# V2_2.net
KiCad netlist of a schematic drawn in EAGLE
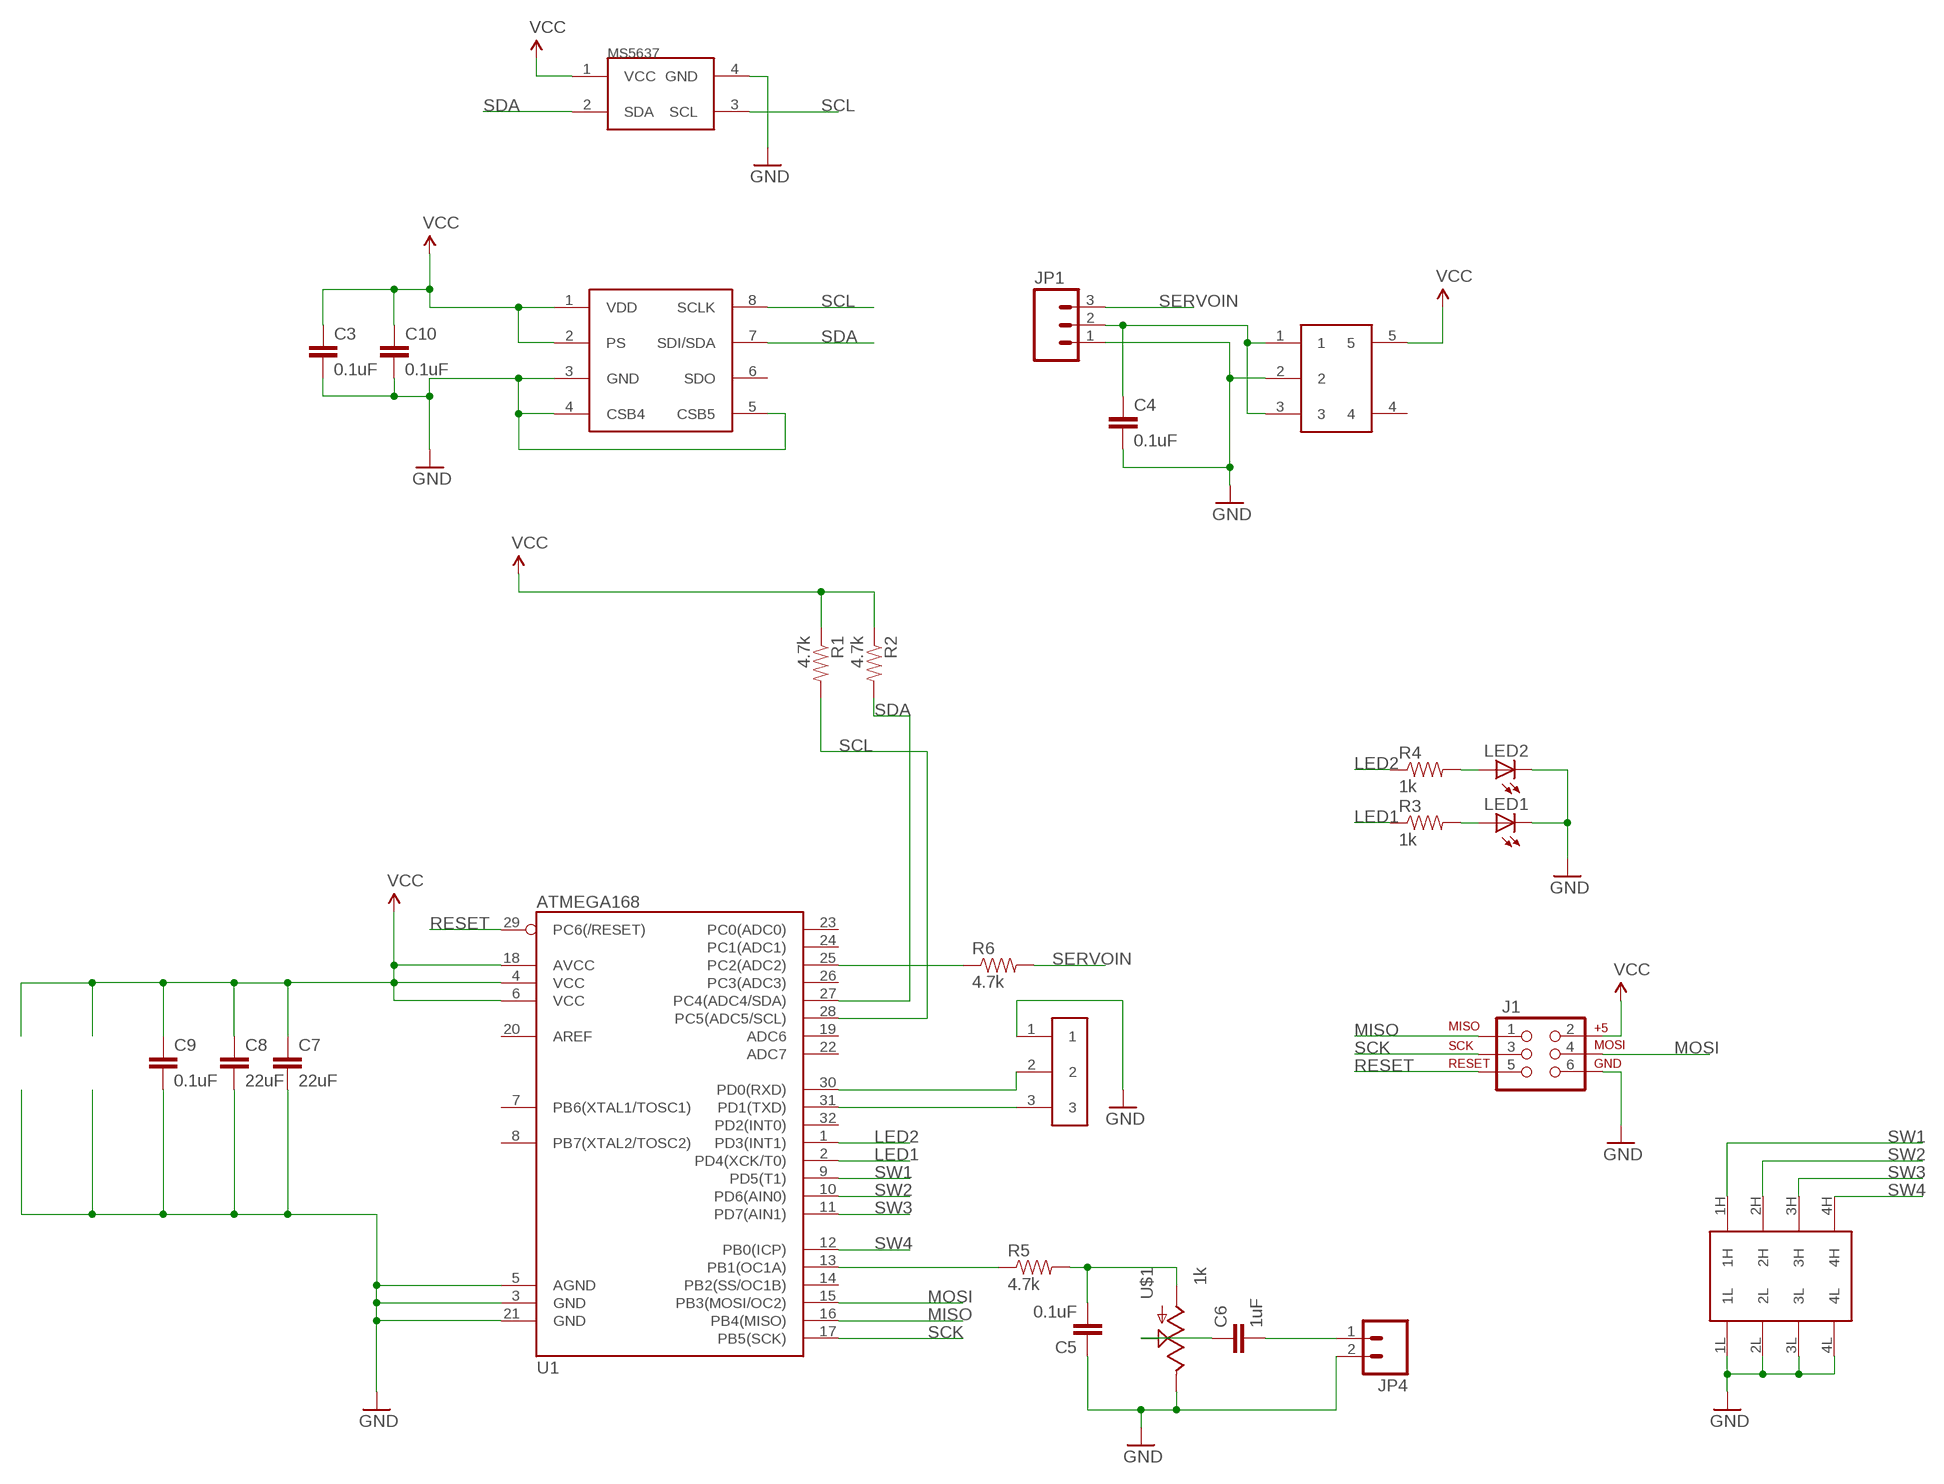
[diagram p0: schematic, sheet 1]

(export (version "E")
  (design (tool "Eeschema 10.0.6"))
  (components
    (comp (ref "C3")
      (value "0.1uF")
      (footprint "eagle-import:0603-CAP")
      (libsource (lib "eagle-import") (part "CAP0603-CAP"))
    )
    (comp (ref "C4")
      (value "0.1uF")
      (footprint "eagle-import:0603-CAP")
      (libsource (lib "eagle-import") (part "CAP0603-CAP"))
    )
    (comp (ref "C5")
      (value "0.1uF")
      (footprint "eagle-import:0603-CAP")
      (libsource (lib "eagle-import") (part "CAP0603-CAP"))
    )
    (comp (ref "C6")
      (value "1uF")
      (footprint "eagle-import:0603-CAP")
      (libsource (lib "eagle-import") (part "CAP0603-CAP"))
    )
    (comp (ref "C7")
      (value "22uF")
      (footprint "eagle-import:0805")
      (libsource (lib "eagle-import") (part "CAP0805"))
    )
    (comp (ref "C8")
      (value "22uF")
      (footprint "eagle-import:0805")
      (libsource (lib "eagle-import") (part "CAP0805"))
    )
    (comp (ref "C9")
      (value "0.1uF")
      (footprint "eagle-import:0603-CAP")
      (libsource (lib "eagle-import") (part "CAP0603-CAP"))
    )
    (comp (ref "C10")
      (value "0.1uF")
      (footprint "eagle-import:0603-CAP")
      (libsource (lib "eagle-import") (part "CAP0603-CAP"))
    )
    (comp (ref "J1")
      (value "AVR_SPI_PRG_6NS")
      (footprint "eagle-import:2X3-NS")
      (libsource (lib "eagle-import") (part "AVR_SPI_PRG_6NS"))
    )
    (comp (ref "JP1")
      (value "M03PTH")
      (footprint "eagle-import:1X03")
      (libsource (lib "eagle-import") (part "M03PTH"))
    )
    (comp (ref "JP4")
      (value "M02PTH")
      (footprint "eagle-import:1X02")
      (libsource (lib "eagle-import") (part "M02PTH"))
    )
    (comp (ref "LED1")
      (value "LED0603")
      (footprint "eagle-import:LED-0603")
      (libsource (lib "eagle-import") (part "LED0603"))
    )
    (comp (ref "LED2")
      (value "LED0603")
      (footprint "eagle-import:LED-0603")
      (libsource (lib "eagle-import") (part "LED0603"))
    )
    (comp (ref "R1")
      (value "4.7k")
      (footprint "eagle-import:0603-RES")
      (libsource (lib "eagle-import") (part "RESISTOR0603-RES"))
    )
    (comp (ref "R2")
      (value "4.7k")
      (footprint "eagle-import:0603-RES")
      (libsource (lib "eagle-import") (part "RESISTOR0603-RES"))
    )
    (comp (ref "R3")
      (value "1k")
      (footprint "eagle-import:0603-RES")
      (libsource (lib "eagle-import") (part "RESISTOR0603-RES"))
    )
    (comp (ref "R4")
      (value "1k")
      (footprint "eagle-import:0603-RES")
      (libsource (lib "eagle-import") (part "RESISTOR0603-RES"))
    )
    (comp (ref "R5")
      (value "4.7k")
      (footprint "eagle-import:0603-RES")
      (libsource (lib "eagle-import") (part "RESISTOR0603-RES"))
    )
    (comp (ref "R6")
      (value "4.7k")
      (footprint "eagle-import:0603-RES")
      (libsource (lib "eagle-import") (part "RESISTOR0603-RES"))
    )
    (comp (ref "U$1")
      (value "1k")
      (footprint "eagle-import:BOURNS_3306KPW")
      (libsource (lib "eagle-import") (part "POTBOURNS_3306KPW"))
    )
    (comp (ref "U$2")
      (value "MS5611")
      (footprint "eagle-import:MS5611")
      (libsource (lib "eagle-import") (part "MS5611"))
    )
    (comp (ref "U$4")
      (value "MS5637")
      (footprint "eagle-import:MS5637")
      (libsource (lib "eagle-import") (part "MS5637"))
    )
    (comp (ref "U$5")
      (value "DIP_SWITCH")
      (footprint "eagle-import:DIPSWITCH4")
      (libsource (lib "eagle-import") (part "DIP_SWITCH"))
    )
    (comp (ref "U$6")
      (value "HEADER3")
      (footprint "eagle-import:PAD3_1X1")
      (libsource (lib "eagle-import") (part "HEADER3"))
    )
    (comp (ref "U$7")
      (value "SOT23-5")
      (footprint "eagle-import:SOT23-5")
      (libsource (lib "eagle-import") (part "SOT23-5"))
    )
    (comp (ref "U1")
      (value "ATMEGA168")
      (footprint "eagle-import:TQFP32-08")
      (libsource (lib "eagle-import") (part "ATMEGA168"))
    )
  )
  (nets
    (net (code "1") (name "/LED1") (class "Default")
      (node (ref "R3") (pin "1") (pinfunction "1_1") (pintype "passive"))
      (node (ref "U1") (pin "2") (pinfunction "PD4(XCK/T0)_2") (pintype "bidirectional"))
    )
    (net (code "2") (name "/LED2") (class "Default")
      (node (ref "R4") (pin "1") (pinfunction "1_1") (pintype "passive"))
      (node (ref "U1") (pin "1") (pinfunction "PD3(INT1)_1") (pintype "bidirectional"))
    )
    (net (code "3") (name "/MISO") (class "Default")
      (node (ref "J1") (pin "1") (pinfunction "1_1") (pintype "passive"))
      (node (ref "U1") (pin "16") (pinfunction "PB4(MISO)_16") (pintype "bidirectional"))
    )
    (net (code "4") (name "/MOSI") (class "Default")
      (node (ref "J1") (pin "4") (pinfunction "4_4") (pintype "passive"))
      (node (ref "U1") (pin "15") (pinfunction "PB3(MOSI/OC2)_15") (pintype "bidirectional"))
    )
    (net (code "5") (name "/RESET") (class "Default")
      (node (ref "J1") (pin "5") (pinfunction "5_5") (pintype "passive"))
      (node (ref "U1") (pin "29") (pinfunction "PC6(/RESET)_29") (pintype "bidirectional"))
    )
    (net (code "6") (name "/SCK") (class "Default")
      (node (ref "J1") (pin "3") (pinfunction "3_3") (pintype "passive"))
      (node (ref "U1") (pin "17") (pinfunction "PB5(SCK)_17") (pintype "bidirectional"))
    )
    (net (code "7") (name "/SCL") (class "Default")
      (node (ref "R1") (pin "2") (pinfunction "2_2") (pintype "passive"))
      (node (ref "U$2") (pin "8") (pinfunction "SCLK_8") (pintype "bidirectional"))
      (node (ref "U$4") (pin "3") (pinfunction "SCL_3") (pintype "bidirectional"))
      (node (ref "U1") (pin "28") (pinfunction "PC5(ADC5/SCL)_28") (pintype "bidirectional"))
    )
    (net (code "8") (name "/SDA") (class "Default")
      (node (ref "R2") (pin "2") (pinfunction "2_2") (pintype "passive"))
      (node (ref "U$2") (pin "7") (pinfunction "SDI/SDA_7") (pintype "bidirectional"))
      (node (ref "U$4") (pin "2") (pinfunction "SDA_2") (pintype "bidirectional"))
      (node (ref "U1") (pin "27") (pinfunction "PC4(ADC4/SDA)_27") (pintype "bidirectional"))
    )
    (net (code "9") (name "/SERVOIN") (class "Default")
      (node (ref "JP1") (pin "3") (pinfunction "3_3") (pintype "passive"))
      (node (ref "R6") (pin "2") (pinfunction "2_2") (pintype "passive"))
    )
    (net (code "10") (name "/SW1") (class "Default")
      (node (ref "U$5") (pin "1H") (pinfunction "1H_1H") (pintype "bidirectional"))
      (node (ref "U1") (pin "9") (pinfunction "PD5(T1)_9") (pintype "bidirectional"))
    )
    (net (code "11") (name "/SW2") (class "Default")
      (node (ref "U$5") (pin "2H") (pinfunction "2H_2H") (pintype "bidirectional"))
      (node (ref "U1") (pin "10") (pinfunction "PD6(AIN0)_10") (pintype "bidirectional"))
    )
    (net (code "12") (name "/SW3") (class "Default")
      (node (ref "U$5") (pin "3H") (pinfunction "3H_3H") (pintype "bidirectional"))
      (node (ref "U1") (pin "11") (pinfunction "PD7(AIN1)_11") (pintype "bidirectional"))
    )
    (net (code "13") (name "/SW4") (class "Default")
      (node (ref "U$5") (pin "4H") (pinfunction "4H_4H") (pintype "bidirectional"))
      (node (ref "U1") (pin "12") (pinfunction "PB0(ICP)_12") (pintype "bidirectional"))
    )
    (net (code "14") (name "GND") (class "Default")
      (node (ref "C10") (pin "2") (pinfunction "2_2") (pintype "passive"))
      (node (ref "C3") (pin "2") (pinfunction "2_2") (pintype "passive"))
      (node (ref "C4") (pin "2") (pinfunction "2_2") (pintype "passive"))
      (node (ref "C5") (pin "1") (pinfunction "1_1") (pintype "passive"))
      (node (ref "C7") (pin "2") (pinfunction "2_2") (pintype "passive"))
      (node (ref "C8") (pin "2") (pinfunction "2_2") (pintype "passive"))
      (node (ref "C9") (pin "2") (pinfunction "2_2") (pintype "passive"))
      (node (ref "J1") (pin "6") (pinfunction "6_6") (pintype "passive"))
      (node (ref "JP1") (pin "1") (pinfunction "1_1") (pintype "passive"))
      (node (ref "JP4") (pin "2") (pinfunction "2_2") (pintype "passive"))
      (node (ref "LED1") (pin "C") (pinfunction "C_C") (pintype "passive"))
      (node (ref "LED2") (pin "C") (pinfunction "C_C") (pintype "passive"))
      (node (ref "U$1") (pin "1") (pinfunction "E_1") (pintype "passive"))
      (node (ref "U$2") (pin "3") (pinfunction "GND_3") (pintype "bidirectional"))
      (node (ref "U$2") (pin "4") (pinfunction "CSB4_4") (pintype "bidirectional"))
      (node (ref "U$2") (pin "5") (pinfunction "CSB5_5") (pintype "bidirectional"))
      (node (ref "U$4") (pin "4") (pinfunction "GND_4") (pintype "bidirectional"))
      (node (ref "U$5") (pin "1L") (pinfunction "1L_1L") (pintype "bidirectional"))
      (node (ref "U$5") (pin "2L") (pinfunction "2L_2L") (pintype "bidirectional"))
      (node (ref "U$5") (pin "3L") (pinfunction "3L_3L") (pintype "bidirectional"))
      (node (ref "U$5") (pin "4L") (pinfunction "4L_4L") (pintype "bidirectional"))
      (node (ref "U$6") (pin "1") (pinfunction "1_1") (pintype "bidirectional"))
      (node (ref "U$7") (pin "2") (pinfunction "2_2") (pintype "bidirectional"))
      (node (ref "U1") (pin "21") (pinfunction "GND_21") (pintype "bidirectional"))
      (node (ref "U1") (pin "3") (pinfunction "GND_3") (pintype "bidirectional"))
      (node (ref "U1") (pin "5") (pinfunction "AGND_5") (pintype "bidirectional"))
    )
    (net (code "15") (name "Net-(C4-Pad1)") (class "Default")
      (node (ref "C4") (pin "1") (pinfunction "1_1") (pintype "passive"))
      (node (ref "JP1") (pin "2") (pinfunction "2_2") (pintype "passive"))
      (node (ref "U$7") (pin "1") (pinfunction "1_1") (pintype "bidirectional"))
      (node (ref "U$7") (pin "3") (pinfunction "3_3") (pintype "bidirectional"))
    )
    (net (code "16") (name "Net-(C6-Pad2)") (class "Default")
      (node (ref "C6") (pin "2") (pinfunction "2_2") (pintype "passive"))
      (node (ref "JP4") (pin "1") (pinfunction "1_1") (pintype "passive"))
    )
    (net (code "17") (name "Net-(LED1-PadA)") (class "Default")
      (node (ref "LED1") (pin "A") (pinfunction "A_A") (pintype "passive"))
      (node (ref "R3") (pin "2") (pinfunction "2_2") (pintype "passive"))
    )
    (net (code "18") (name "Net-(LED2-PadA)") (class "Default")
      (node (ref "LED2") (pin "A") (pinfunction "A_A") (pintype "passive"))
      (node (ref "R4") (pin "2") (pinfunction "2_2") (pintype "passive"))
    )
    (net (code "19") (name "Net-(U$1-A)") (class "Default")
      (node (ref "C5") (pin "2") (pinfunction "2_2") (pintype "passive"))
      (node (ref "R5") (pin "2") (pinfunction "2_2") (pintype "passive"))
      (node (ref "U$1") (pin "3") (pinfunction "A_3") (pintype "passive"))
    )
    (net (code "20") (name "Net-(U$1-S)") (class "Default")
      (node (ref "C6") (pin "1") (pinfunction "1_1") (pintype "passive"))
      (node (ref "U$1") (pin "2") (pinfunction "S_2") (pintype "passive"))
    )
    (net (code "21") (name "Net-(U1-PB1(OC1A))") (class "Default")
      (node (ref "R5") (pin "1") (pinfunction "1_1") (pintype "passive"))
      (node (ref "U1") (pin "13") (pinfunction "PB1(OC1A)_13") (pintype "bidirectional"))
    )
    (net (code "22") (name "Net-(U1-PC2(ADC2))") (class "Default")
      (node (ref "R6") (pin "1") (pinfunction "1_1") (pintype "passive"))
      (node (ref "U1") (pin "25") (pinfunction "PC2(ADC2)_25") (pintype "bidirectional"))
    )
    (net (code "23") (name "Net-(U1-PD0(RXD))") (class "Default")
      (node (ref "U$6") (pin "2") (pinfunction "2_2") (pintype "bidirectional"))
      (node (ref "U1") (pin "30") (pinfunction "PD0(RXD)_30") (pintype "bidirectional"))
    )
    (net (code "24") (name "Net-(U1-PD1(TXD))") (class "Default")
      (node (ref "U$6") (pin "3") (pinfunction "3_3") (pintype "bidirectional"))
      (node (ref "U1") (pin "31") (pinfunction "PD1(TXD)_31") (pintype "bidirectional"))
    )
    (net (code "25") (name "VCC") (class "Default")
      (node (ref "C10") (pin "1") (pinfunction "1_1") (pintype "passive"))
      (node (ref "C3") (pin "1") (pinfunction "1_1") (pintype "passive"))
      (node (ref "C7") (pin "1") (pinfunction "1_1") (pintype "passive"))
      (node (ref "C8") (pin "1") (pinfunction "1_1") (pintype "passive"))
      (node (ref "C9") (pin "1") (pinfunction "1_1") (pintype "passive"))
      (node (ref "J1") (pin "2") (pinfunction "2_2") (pintype "passive"))
      (node (ref "R1") (pin "1") (pinfunction "1_1") (pintype "passive"))
      (node (ref "R2") (pin "1") (pinfunction "1_1") (pintype "passive"))
      (node (ref "U$2") (pin "1") (pinfunction "VDD_1") (pintype "bidirectional"))
      (node (ref "U$2") (pin "2") (pinfunction "PS_2") (pintype "bidirectional"))
      (node (ref "U$4") (pin "1") (pinfunction "VCC_1") (pintype "bidirectional"))
      (node (ref "U$7") (pin "5") (pinfunction "5_5") (pintype "bidirectional"))
      (node (ref "U1") (pin "18") (pinfunction "AVCC_18") (pintype "bidirectional"))
      (node (ref "U1") (pin "4") (pinfunction "VCC_4") (pintype "bidirectional"))
      (node (ref "U1") (pin "6") (pinfunction "VCC_6") (pintype "bidirectional"))
    )
    (net (code "26") (name "unconnected-(U$2-SDO-Pad6)") (class "Default")
      (node (ref "U$2") (pin "6") (pinfunction "SDO_6") (pintype "bidirectional"))
    )
    (net (code "27") (name "unconnected-(U$7-Pad4)") (class "Default")
      (node (ref "U$7") (pin "4") (pinfunction "4_4") (pintype "bidirectional"))
    )
    (net (code "28") (name "unconnected-(U1-ADC6-Pad19)") (class "Default")
      (node (ref "U1") (pin "19") (pinfunction "ADC6_19") (pintype "bidirectional"))
    )
    (net (code "29") (name "unconnected-(U1-ADC7-Pad22)") (class "Default")
      (node (ref "U1") (pin "22") (pinfunction "ADC7_22") (pintype "bidirectional"))
    )
    (net (code "30") (name "unconnected-(U1-AREF-Pad20)") (class "Default")
      (node (ref "U1") (pin "20") (pinfunction "AREF_20") (pintype "bidirectional"))
    )
    (net (code "31") (name "unconnected-(U1-PB2(SS{slash}OC1B)-Pad14)") (class "Default")
      (node (ref "U1") (pin "14") (pinfunction "PB2(SS/OC1B)_14") (pintype "bidirectional"))
    )
    (net (code "32") (name "unconnected-(U1-PB6(XTAL1{slash}TOSC1)-Pad7)") (class "Default")
      (node (ref "U1") (pin "7") (pinfunction "PB6(XTAL1/TOSC1)_7") (pintype "bidirectional"))
    )
    (net (code "33") (name "unconnected-(U1-PB7(XTAL2{slash}TOSC2)-Pad8)") (class "Default")
      (node (ref "U1") (pin "8") (pinfunction "PB7(XTAL2/TOSC2)_8") (pintype "bidirectional"))
    )
    (net (code "34") (name "unconnected-(U1-PC0(ADC0)-Pad23)") (class "Default")
      (node (ref "U1") (pin "23") (pinfunction "PC0(ADC0)_23") (pintype "bidirectional"))
    )
    (net (code "35") (name "unconnected-(U1-PC1(ADC1)-Pad24)") (class "Default")
      (node (ref "U1") (pin "24") (pinfunction "PC1(ADC1)_24") (pintype "bidirectional"))
    )
    (net (code "36") (name "unconnected-(U1-PC3(ADC3)-Pad26)") (class "Default")
      (node (ref "U1") (pin "26") (pinfunction "PC3(ADC3)_26") (pintype "bidirectional"))
    )
    (net (code "37") (name "unconnected-(U1-PD2(INT0)-Pad32)") (class "Default")
      (node (ref "U1") (pin "32") (pinfunction "PD2(INT0)_32") (pintype "bidirectional"))
    )
  )
)
